# USB_DockingSTN.net
KiCad netlist of a schematic drawn in Altium Designer
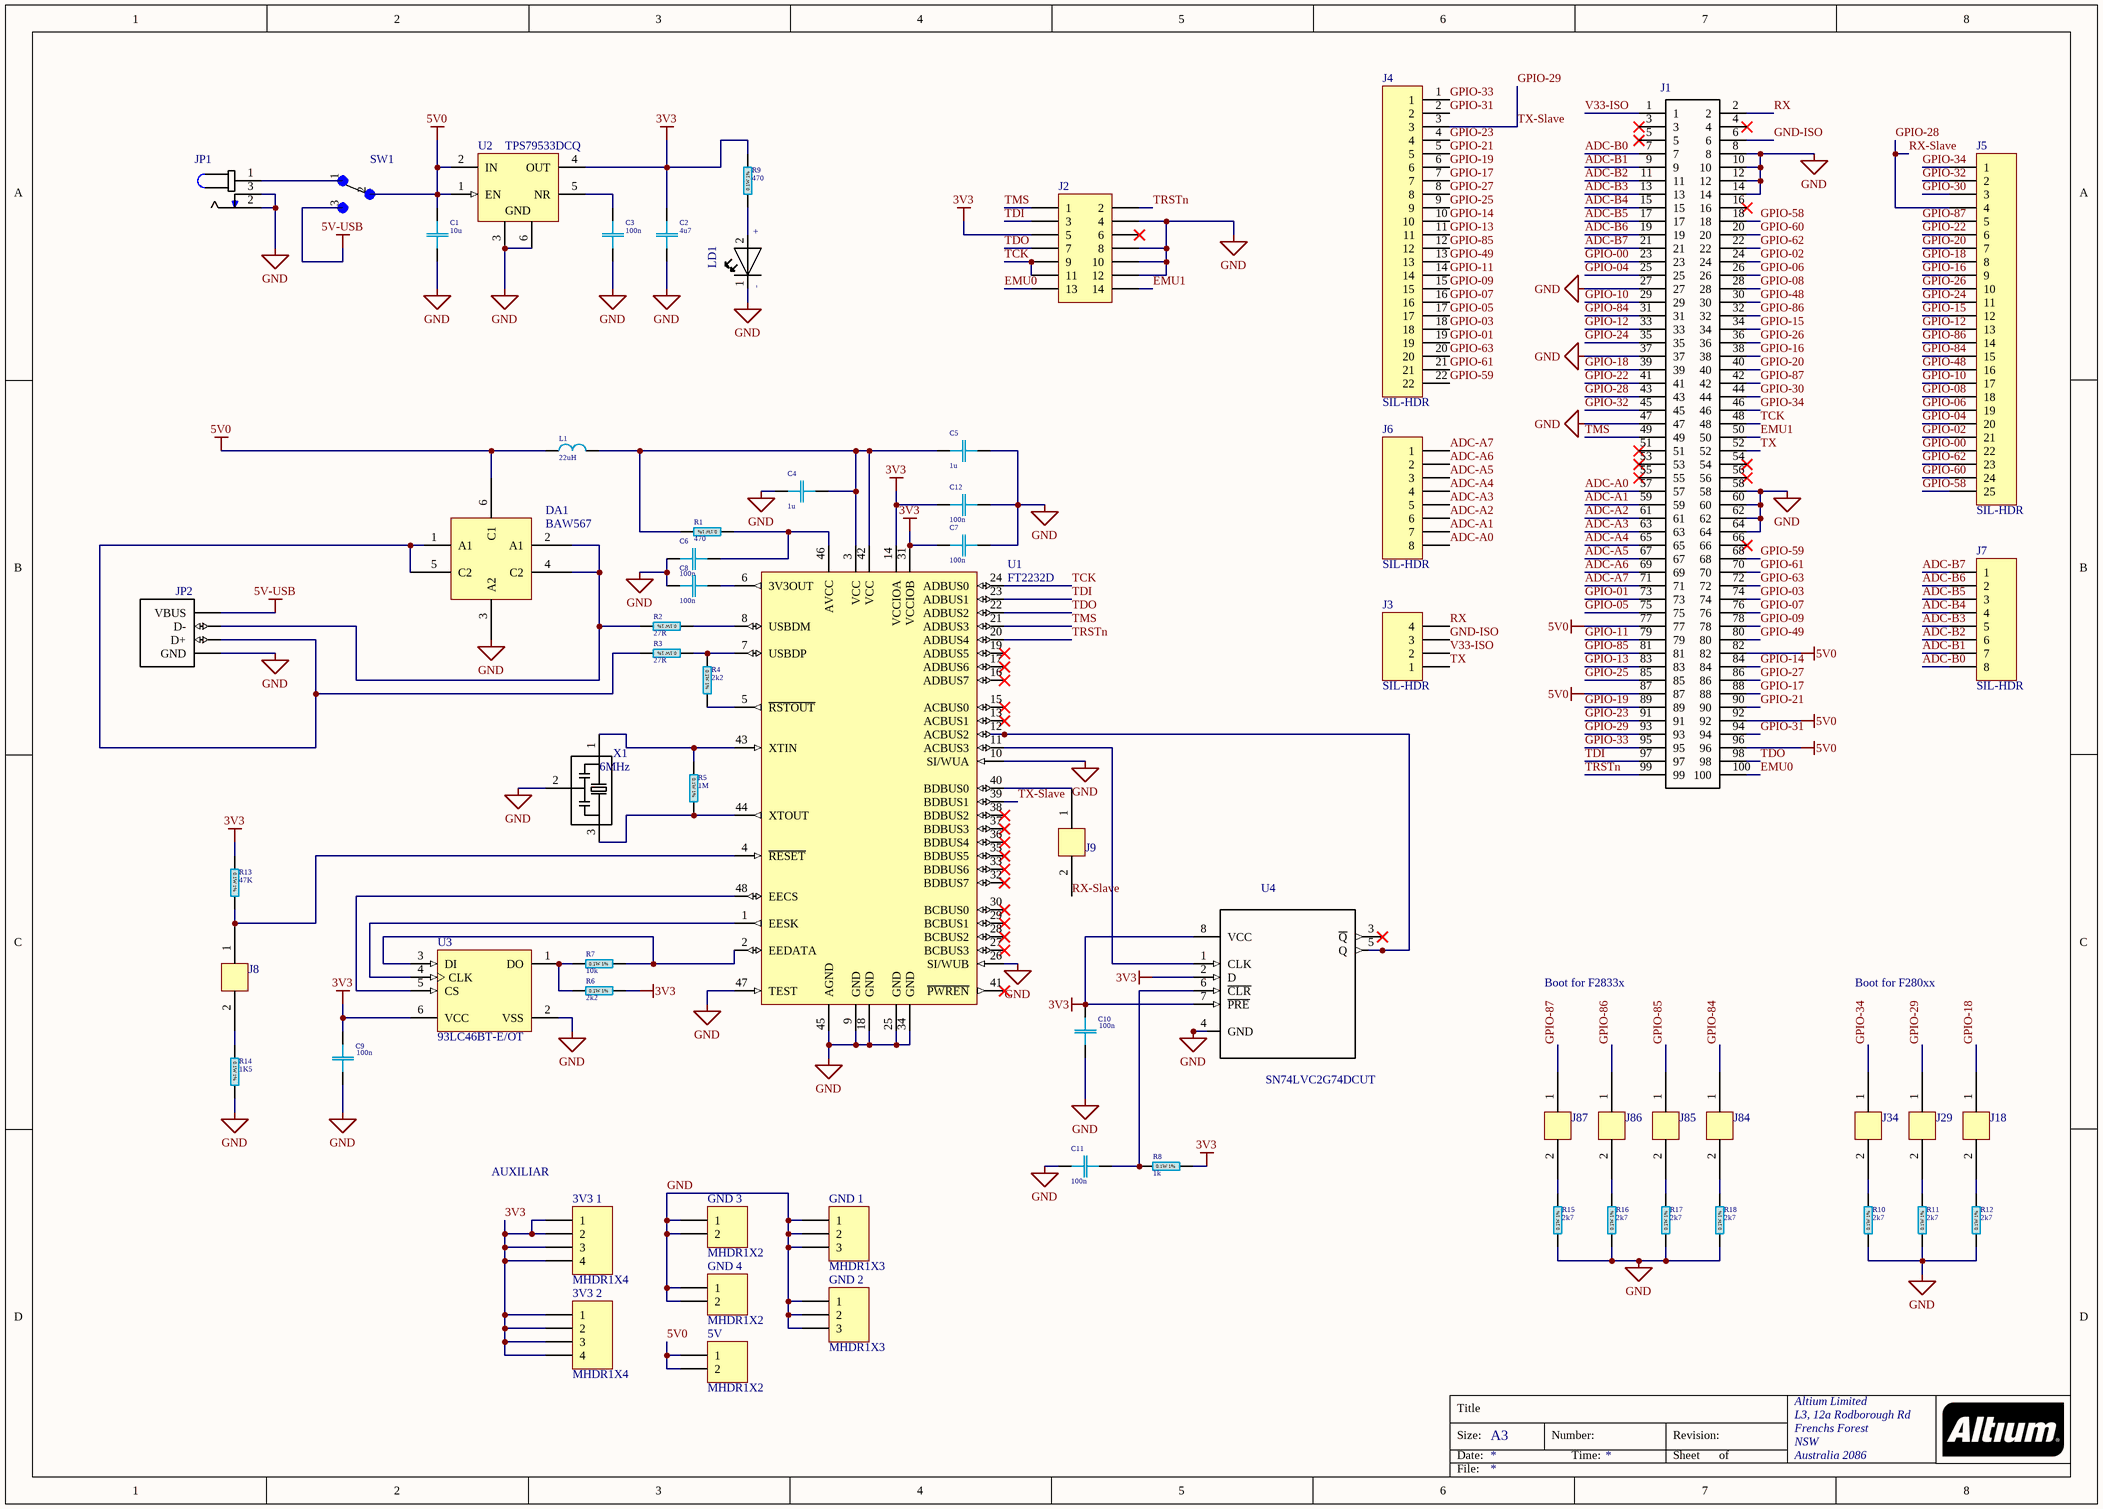
[diagram p0: USB_DockingSTN.SchDoc]

(export (version "E")
  (design (tool "Eeschema 10.0.6"))
  (components
    (comp (ref "3V3 1")
      (value "MHDR1X4")
      (footprint "MHDR1X4")
      (description "Header, 4-Pin")
      (fields (field (name "PUBLISHER") "Altium Limited"))
      (libsource (lib "Miscellaneous Connectors") (part "MHDR1X4"))
    )
    (comp (ref "3V3 2")
      (value "MHDR1X4")
      (footprint "MHDR1X4")
      (description "Header, 4-Pin")
      (fields (field (name "PUBLISHER") "Altium Limited"))
      (libsource (lib "Miscellaneous Connectors") (part "MHDR1X4"))
    )
    (comp (ref "5V")
      (value "MHDR1X2")
      (footprint "MHDR1X2")
      (description "Header, 2-Pin")
      (fields (field (name "PUBLISHER") "Altium Limited"))
      (libsource (lib "Miscellaneous Connectors") (part "MHDR1X2"))
    )
    (comp (ref "C1")
      (value "10u")
      (footprint "C 0805(2012)x0.65")
      (description "SMD-0805   100V X7R 10%")
      (fields
        (field (name "PART NUMBER") "CL21B103KCNC")
        (field (name "MANUFACTURER") "Samsung")
        (field (name "PUBLISHER") "Hefest")
      )
      (libsource (lib "SMD-Passive_ShareAppsCrack.com") (part "C 0805  100V X7R - 10n"))
    )
    (comp (ref "C2")
      (value "~")
      (footprint "C 0805(2012)x0.65")
      (description "SMD-0805   100V X7R 10%")
      (fields
        (field (name "PART NUMBER") "CL21B103KCNC")
        (field (name "MANUFACTURER") "Samsung")
        (field (name "0N") "4u7")
        (field (name "PUBLISHER") "Hefest")
      )
      (libsource (lib "SMD-Passive_ShareAppsCrack.com") (part "C 0805  100V X7R - 10n"))
    )
    (comp (ref "C3")
      (value "~")
      (footprint "C 0805(2012)x0.65")
      (description "SMD-0805   100V X7R 10%")
      (fields
        (field (name "PART NUMBER") "CL21B103KCNC")
        (field (name "MANUFACTURER") "Samsung")
        (field (name "0N") "100n")
        (field (name "PUBLISHER") "Hefest")
      )
      (libsource (lib "SMD-Passive_ShareAppsCrack.com") (part "C 0805  100V X7R - 10n"))
    )
    (comp (ref "C4")
      (value "1u")
      (footprint "C 0603(1608)x0.8")
      (description "SMD-0603     16V X5R 10%")
      (fields (field (name "MANUFACTURER") "Samsung") (field (name "PUBLISHER") "Hefest"))
      (libsource (lib "SMD-Passive_ShareAppsCrack.com") (part "C 0603    16V X7R - 1u"))
    )
    (comp (ref "C5")
      (value "1u")
      (footprint "C 0603(1608)x0.8")
      (description "SMD-0603     16V X5R 10%")
      (fields (field (name "MANUFACTURER") "Samsung") (field (name "PUBLISHER") "Hefest"))
      (libsource (lib "SMD-Passive_ShareAppsCrack.com") (part "C 0603    16V X7R - 1u"))
    )
    (comp (ref "C6")
      (value "100n")
      (footprint "C 0603(1608)x0.8")
      (description "SMD-0603     16V X5R 10%")
      (fields (field (name "MANUFACTURER") "Samsung") (field (name "PUBLISHER") "Hefest"))
      (libsource (lib "SMD-Passive_ShareAppsCrack.com") (part "C 0603    16V X7R - 1u"))
    )
    (comp (ref "C7")
      (value "100n")
      (footprint "C 0603(1608)x0.8")
      (description "SMD-0603     16V X5R 10%")
      (fields (field (name "MANUFACTURER") "Samsung") (field (name "PUBLISHER") "Hefest"))
      (libsource (lib "SMD-Passive_ShareAppsCrack.com") (part "C 0603    16V X7R - 1u"))
    )
    (comp (ref "C8")
      (value "100n")
      (footprint "C 0603(1608)x0.8")
      (description "SMD-0603     16V X5R 10%")
      (fields (field (name "MANUFACTURER") "Samsung") (field (name "PUBLISHER") "Hefest"))
      (libsource (lib "SMD-Passive_ShareAppsCrack.com") (part "C 0603    16V X7R - 1u"))
    )
    (comp (ref "C9")
      (value "100n")
      (footprint "C 0603(1608)x0.8")
      (description "SMD-0603     16V X5R 10%")
      (fields (field (name "MANUFACTURER") "Samsung") (field (name "PUBLISHER") "Hefest"))
      (libsource (lib "SMD-Passive_ShareAppsCrack.com") (part "C 0603    16V X7R - 1u"))
    )
    (comp (ref "C10")
      (value "100n")
      (footprint "C 0603(1608)x0.8")
      (description "SMD-0603     16V X5R 10%")
      (fields (field (name "MANUFACTURER") "Samsung") (field (name "PUBLISHER") "Hefest"))
      (libsource (lib "SMD-Passive_ShareAppsCrack.com") (part "C 0603    16V X7R - 1u"))
    )
    (comp (ref "C11")
      (value "100n")
      (footprint "C 0603(1608)x0.8")
      (description "SMD-0603     16V X5R 10%")
      (fields (field (name "MANUFACTURER") "Samsung") (field (name "PUBLISHER") "Hefest"))
      (libsource (lib "SMD-Passive_ShareAppsCrack.com") (part "C 0603    16V X7R - 1u"))
    )
    (comp (ref "C12")
      (value "100n")
      (footprint "C 0603(1608)x0.8")
      (description "SMD-0603     16V X5R 10%")
      (fields (field (name "MANUFACTURER") "Samsung") (field (name "PUBLISHER") "Hefest"))
      (libsource (lib "SMD-Passive_ShareAppsCrack.com") (part "C 0603    16V X7R - 1u"))
    )
    (comp (ref "DA1") (value "BAW567") (footprint "BAW567") (libsource (lib "Schlib2") (part "A1")))
    (comp (ref "GND 1")
      (value "MHDR1X3")
      (footprint "MHDR1X3")
      (description "Header, 3-Pin")
      (fields (field (name "PUBLISHER") "Altium Limited"))
      (libsource (lib "Miscellaneous Connectors") (part "MHDR1X3"))
    )
    (comp (ref "GND 2")
      (value "MHDR1X3")
      (footprint "MHDR1X3")
      (description "Header, 3-Pin")
      (fields (field (name "PUBLISHER") "Altium Limited"))
      (libsource (lib "Miscellaneous Connectors") (part "MHDR1X3"))
    )
    (comp (ref "GND 3")
      (value "MHDR1X2")
      (footprint "MHDR1X2")
      (description "Header, 2-Pin")
      (fields (field (name "PUBLISHER") "Altium Limited"))
      (libsource (lib "Miscellaneous Connectors") (part "MHDR1X2"))
    )
    (comp (ref "GND 4")
      (value "MHDR1X2")
      (footprint "MHDR1X2")
      (description "Header, 2-Pin")
      (fields (field (name "PUBLISHER") "Altium Limited"))
      (libsource (lib "Miscellaneous Connectors") (part "MHDR1X2"))
    )
    (comp (ref "J1")
      (value "5390213-1")
      (footprint "*TE_5390213-1")
      (description "D2P,100 POS,3.3V,NB DRAM,PB-FREE")
      (fields (field (name "MF") "TE Connectivity"))
      (libsource (lib "5390213-1") (part "5390213-1"))
    )
    (comp (ref "J2")
      (value "MHDR2X7")
      (footprint "MHDR2X7")
      (description "Header, 7-Pin, Dual row")
      (fields (field (name "PUBLISHER") "Altium Limited"))
      (libsource (lib "Miscellaneous Connectors") (part "MHDR2X7"))
    )
    (comp (ref "J3")
      (value "SIL-HDR")
      (footprint "MHDR1X4")
      (description "Header, 4-Pin")
      (fields (field (name "PUBLISHER") "Altium Limited"))
      (libsource (lib "") (part "MHDR1X4_1"))
    )
    (comp (ref "J4")
      (value "SIL-HDR")
      (footprint "PIN22")
      (description "22-Pin Edge Connector")
      (fields (field (name "PUBLISHER") "Altium Limited"))
      (libsource (lib "Miscellaneous Connectors") (part "Edge Con 22"))
    )
    (comp (ref "J5")
      (value "SIL-HDR")
      (footprint "HDR1X25")
      (description "Header, 25-Pin")
      (fields (field (name "PUBLISHER") "Altium Limited"))
      (libsource (lib "Miscellaneous Connectors") (part "Header 25"))
    )
    (comp (ref "J6")
      (value "SIL-HDR")
      (footprint "MHDR1X8")
      (description "Header, 8-Pin")
      (fields (field (name "PUBLISHER") "Altium Limited"))
      (libsource (lib "Miscellaneous Connectors") (part "MHDR1X8"))
    )
    (comp (ref "J7")
      (value "SIL-HDR")
      (footprint "MHDR1X8")
      (description "Header, 8-Pin")
      (fields (field (name "PUBLISHER") "Altium Limited"))
      (libsource (lib "") (part "MHDR1X8_1"))
    )
    (comp (ref "J8")
      (value "~")
      (footprint "PCBComponent_1")
      (libsource (lib "connector 2") (part "Component_1"))
    )
    (comp (ref "J9")
      (value "J9")
      (footprint "PCBComponent_1")
      (libsource (lib "connector 2") (part "Component_1"))
    )
    (comp (ref "J18")
      (value "~")
      (footprint "PCBComponent_1")
      (libsource (lib "connector 2") (part "Component_1"))
    )
    (comp (ref "J29")
      (value "~")
      (footprint "PCBComponent_1")
      (libsource (lib "connector 2") (part "Component_1"))
    )
    (comp (ref "J34")
      (value "~")
      (footprint "PCBComponent_1")
      (libsource (lib "connector 2") (part "Component_1"))
    )
    (comp (ref "J84")
      (value "~")
      (footprint "PCBComponent_1")
      (libsource (lib "connector 2") (part "Component_1"))
    )
    (comp (ref "J85")
      (value "~")
      (footprint "PCBComponent_1")
      (libsource (lib "connector 2") (part "Component_1"))
    )
    (comp (ref "J86")
      (value "~")
      (footprint "PCBComponent_1")
      (libsource (lib "connector 2") (part "Component_1"))
    )
    (comp (ref "J87")
      (value "~")
      (footprint "PCBComponent_1")
      (libsource (lib "connector 2") (part "Component_1"))
    )
    (comp (ref "JP1")
      (value "PJ-002BH")
      (footprint "*CUI_PJ-002BH")
      (description "2.5 x 6.5 mm, 5.0 A, Horizontal, Through Hole, Dc Power Jack Connector")
      (fields (field (name "MF") "CUI Devices") (field (name "DIGI-KEY_PART_NUMBER") "CP-002BH-ND"))
      (libsource (lib "PJ-002BH") (part "PJ-002BH"))
    )
    (comp (ref "JP2")
      (value "292304-1")
      (footprint "*TE_292304-1")
      (description "USB - B USB 2.0 Receptacle Connector 4 Position Through Hole, Right Angle")
      (fields (field (name "MF") "TE Connectivity"))
      (libsource (lib "292304-1") (part "292304-1"))
    )
    (comp (ref "L1")
      (value "22uH")
      (footprint "L 0805(2012)")
      (description "SMD 0805 Q-65 @150MHz")
      (fields
        (field (name "PART NUMBER") "CCFH0805 C R10J")
        (field (name "MANUFACTURER") "COILS")
        (field (name "PUBLISHER") "Hefest")
      )
      (libsource (lib "SMD-Passive_ShareAppsCrack.com") (part "L 0805 100n"))
    )
    (comp (ref "LD1")
      (value "WL-SMCW")
      (footprint "*WL-SMCW_0603")
      (description "LED, 0805, B GREEN, 40MCD, 570NM; Bulb Size: -; LED Colour: Green; Luminous Intens")
      (fields (field (name "MF") "Wurth Electronics") (field (name "DIGI-KEY_PART_NUMBER") "732-4986-1-ND"))
      (libsource (lib "WL-SMCW") (part "WL-SMCW"))
    )
    (comp (ref "R1")
      (value "470")
      (footprint "R 0603(1608)")
      (description "SMD 0603 0.1W     5%   75V")
      (fields
        (field (name "MANUFACTURER") "YAGEO")
        (field (name "POWER") "0.1W")
        (field (name "PUBLISHER") "Hefest")
      )
      (libsource (lib "") (part "R 0603-5%_1"))
    )
    (comp (ref "R2")
      (value "27R")
      (footprint "R 0603(1608)")
      (description "SMD 0603 0.1W     5%   75V")
      (fields
        (field (name "MANUFACTURER") "YAGEO")
        (field (name "POWER") "0.1W")
        (field (name "PUBLISHER") "Hefest")
      )
      (libsource (lib "") (part "R 0603-5%_1"))
    )
    (comp (ref "R3")
      (value "27R")
      (footprint "R 0603(1608)")
      (description "SMD 0603 0.1W     5%   75V")
      (fields
        (field (name "MANUFACTURER") "YAGEO")
        (field (name "POWER") "0.1W")
        (field (name "PUBLISHER") "Hefest")
      )
      (libsource (lib "") (part "R 0603-5%_1"))
    )
    (comp (ref "R4")
      (value "2k2")
      (footprint "R 0603(1608)")
      (description "SMD 0603 0.1W     5%   75V")
      (fields
        (field (name "MANUFACTURER") "YAGEO")
        (field (name "POWER") "0.1W")
        (field (name "PUBLISHER") "Hefest")
      )
      (libsource (lib "SMD-Passive_ShareAppsCrack.com") (part "R 0603-5%"))
    )
    (comp (ref "R5")
      (value "1M")
      (footprint "R 0603(1608)")
      (description "SMD 0603 0.1W     5%   75V")
      (fields
        (field (name "MANUFACTURER") "YAGEO")
        (field (name "POWER") "0.1W")
        (field (name "PUBLISHER") "Hefest")
      )
      (libsource (lib "SMD-Passive_ShareAppsCrack.com") (part "R 0603-5%"))
    )
    (comp (ref "R6")
      (value "2k2")
      (footprint "R 0603(1608)")
      (description "SMD 0603 0.1W     5%   75V")
      (fields
        (field (name "MANUFACTURER") "YAGEO")
        (field (name "POWER") "0.1W")
        (field (name "PUBLISHER") "Hefest")
      )
      (libsource (lib "") (part "R 0603-5%_2"))
    )
    (comp (ref "R7")
      (value "10k")
      (footprint "R 0603(1608)")
      (description "SMD 0603 0.1W     5%   75V")
      (fields
        (field (name "MANUFACTURER") "YAGEO")
        (field (name "POWER") "0.1W")
        (field (name "PUBLISHER") "Hefest")
      )
      (libsource (lib "") (part "R 0603-5%_2"))
    )
    (comp (ref "R8")
      (value "1k")
      (footprint "R 0603(1608)")
      (description "SMD 0603 0.1W     5%   75V")
      (fields
        (field (name "MANUFACTURER") "YAGEO")
        (field (name "POWER") "0.1W")
        (field (name "PUBLISHER") "Hefest")
      )
      (libsource (lib "") (part "R 0603-5%_2"))
    )
    (comp (ref "R9")
      (value "470")
      (footprint "R 0603(1608)")
      (description "SMD 0603 0.1W     5%   75V")
      (fields
        (field (name "MANUFACTURER") "YAGEO")
        (field (name "POWER") "0.1W")
        (field (name "PUBLISHER") "Hefest")
      )
      (libsource (lib "") (part "R 0603-5%_3"))
    )
    (comp (ref "R10")
      (value "2k7")
      (footprint "R 0603(1608)")
      (description "SMD 0603 0.1W     5%   75V")
      (fields
        (field (name "MANUFACTURER") "YAGEO")
        (field (name "POWER") "0.1W")
        (field (name "PUBLISHER") "Hefest")
      )
      (libsource (lib "") (part "R 0603-5%_3"))
    )
    (comp (ref "R11")
      (value "2k7")
      (footprint "R 0603(1608)")
      (description "SMD 0603 0.1W     5%   75V")
      (fields
        (field (name "MANUFACTURER") "YAGEO")
        (field (name "POWER") "0.1W")
        (field (name "PUBLISHER") "Hefest")
      )
      (libsource (lib "") (part "R 0603-5%_3"))
    )
    (comp (ref "R12")
      (value "2k7")
      (footprint "R 0603(1608)")
      (description "SMD 0603 0.1W     5%   75V")
      (fields
        (field (name "MANUFACTURER") "YAGEO")
        (field (name "POWER") "0.1W")
        (field (name "PUBLISHER") "Hefest")
      )
      (libsource (lib "") (part "R 0603-5%_3"))
    )
    (comp (ref "R13")
      (value "47K")
      (footprint "R 0603(1608)")
      (description "SMD 0603 0.1W     5%   75V")
      (fields
        (field (name "MANUFACTURER") "YAGEO")
        (field (name "POWER") "0.1W")
        (field (name "PUBLISHER") "Hefest")
      )
      (libsource (lib "SMD-Passive_ShareAppsCrack.com") (part "R 0603-5%"))
    )
    (comp (ref "R14")
      (value "1K5")
      (footprint "R 0603(1608)")
      (description "SMD 0603 0.1W     5%   75V")
      (fields
        (field (name "MANUFACTURER") "YAGEO")
        (field (name "POWER") "0.1W")
        (field (name "PUBLISHER") "Hefest")
      )
      (libsource (lib "SMD-Passive_ShareAppsCrack.com") (part "R 0603-5%"))
    )
    (comp (ref "R15")
      (value "2k7")
      (footprint "R 0603(1608)")
      (description "SMD 0603 0.1W     5%   75V")
      (fields
        (field (name "MANUFACTURER") "YAGEO")
        (field (name "POWER") "0.1W")
        (field (name "PUBLISHER") "Hefest")
      )
      (libsource (lib "") (part "R 0603-5%_3"))
    )
    (comp (ref "R16")
      (value "2k7")
      (footprint "R 0603(1608)")
      (description "SMD 0603 0.1W     5%   75V")
      (fields
        (field (name "MANUFACTURER") "YAGEO")
        (field (name "POWER") "0.1W")
        (field (name "PUBLISHER") "Hefest")
      )
      (libsource (lib "") (part "R 0603-5%_3"))
    )
    (comp (ref "R17")
      (value "2k7")
      (footprint "R 0603(1608)")
      (description "SMD 0603 0.1W     5%   75V")
      (fields
        (field (name "MANUFACTURER") "YAGEO")
        (field (name "POWER") "0.1W")
        (field (name "PUBLISHER") "Hefest")
      )
      (libsource (lib "") (part "R 0603-5%_3"))
    )
    (comp (ref "R18")
      (value "2k7")
      (footprint "R 0603(1608)")
      (description "SMD 0603 0.1W     5%   75V")
      (fields
        (field (name "MANUFACTURER") "YAGEO")
        (field (name "POWER") "0.1W")
        (field (name "PUBLISHER") "Hefest")
      )
      (libsource (lib "") (part "R 0603-5%_3"))
    )
    (comp (ref "SW1")
      (value "400BWMSP1R2BLKSM6QE")
      (footprint "*SW_400BWMSP1R2BLKSM6QE")
      (description "400B Series 3 A SPDT On-None-On Surface Mount Sub-Miniature Rocker Switch")
      (fields (field (name "MF") "E-Switch"))
      (libsource (lib "400BWMSP1R2BLKSM6QE") (part "400BWMSP1R2BLKSM6QE"))
    )
    (comp (ref "U1")
      (value "FT2232D")
      (footprint "LQFP-48_N")
      (description "FT2232D Dual USB to Serial UART/FIFO IC, -40 to +85 degC, 48-pin LQFP")
      (fields (field (name "MANUFACTURER") "FTDI"))
      (libsource (lib "FTDI FT Series") (part "FT2232D"))
    )
    (comp (ref "U2")
      (value "TPS79533DCQ")
      (footprint "TI-DCQ6_N")
      (fields (field (name "MANUFACTURER") "Texas Instruments"))
      (libsource (lib "TI Power Management Linear Regulator Single Channel LDO (400-7500mA)") (part "TPS79533DCQ"))
    )
    (comp (ref "U3")
      (value "93LC46BT-E/OT")
      (footprint "SOT-23-OT6_N")
      (description "1K, 64x16-bit, 2.5V Microwire Serial EEPROM, 6-Pin SOT-23, Extended Temperature, Tape and Reel")
      (fields (field (name "MANUFACTURER") "Microchip"))
      (libsource (lib "Microchip Microwire Serial EEPROM") (part "93LC46BT-E/OT"))
    )
    (comp (ref "U4")
      (value "SN74LVC2G74DCUT")
      (footprint "*SOP50P310X90-8N")
      (description "Single Positive-Edge-Triggered D-Type Flip-Flop with Clear and Preset 8-VSSOP -40 to 125")
      (fields (field (name "DIGI-KEY_PART_NUMBER") "296-26623-1-ND") (field (name "MF") "Texas Instruments"))
      (libsource (lib "SN74LVC2G74DCUT") (part "SN74LVC2G74DCUT"))
    )
    (comp (ref "X1")
      (value "~")
      (footprint "*OSC_CSTCR4M00G53-R0")
      (description "Ceramic Resonator 4MHz ??0.5% _Tol_ ??0.2% _Stability_ 15pF 60Ohm 3-Pin CSMD T/R")
      (fields (field (name "MP") "CSTCR4M00G53-R0") (field (name "MF") "Murata"))
      (libsource (lib "CSTCR4M00G53-R0") (part "CSTCR4M00G53-R0"))
    )
  )
  (nets
    (net (code "1") (name "/ADC-A0") (class "Default")
      (node (ref "J1") (pin "57") (pinfunction "57_57") (pintype "passive"))
      (node (ref "J6") (pin "8") (pinfunction "8_8") (pintype "passive"))
    )
    (net (code "2") (name "/ADC-A1") (class "Default")
      (node (ref "J1") (pin "59") (pinfunction "59_59") (pintype "passive"))
      (node (ref "J6") (pin "7") (pinfunction "7_7") (pintype "passive"))
    )
    (net (code "3") (name "/ADC-A2") (class "Default")
      (node (ref "J1") (pin "61") (pinfunction "61_61") (pintype "passive"))
      (node (ref "J6") (pin "6") (pinfunction "6_6") (pintype "passive"))
    )
    (net (code "4") (name "/ADC-A3") (class "Default")
      (node (ref "J1") (pin "63") (pinfunction "63_63") (pintype "passive"))
      (node (ref "J6") (pin "5") (pinfunction "5_5") (pintype "passive"))
    )
    (net (code "5") (name "/ADC-A4") (class "Default")
      (node (ref "J1") (pin "65") (pinfunction "65_65") (pintype "passive"))
      (node (ref "J6") (pin "4") (pinfunction "4_4") (pintype "passive"))
    )
    (net (code "6") (name "/ADC-A5") (class "Default")
      (node (ref "J1") (pin "67") (pinfunction "67_67") (pintype "passive"))
      (node (ref "J6") (pin "3") (pinfunction "3_3") (pintype "passive"))
    )
    (net (code "7") (name "/ADC-A6") (class "Default")
      (node (ref "J1") (pin "69") (pinfunction "69_69") (pintype "passive"))
      (node (ref "J6") (pin "2") (pinfunction "2_2") (pintype "passive"))
    )
    (net (code "8") (name "/ADC-A7") (class "Default")
      (node (ref "J1") (pin "71") (pinfunction "71_71") (pintype "passive"))
      (node (ref "J6") (pin "1") (pinfunction "1_1") (pintype "passive"))
    )
    (net (code "9") (name "/ADC-B0") (class "Default")
      (node (ref "J1") (pin "7") (pinfunction "7_7") (pintype "passive"))
      (node (ref "J7") (pin "8") (pinfunction "8_8") (pintype "passive"))
    )
    (net (code "10") (name "/ADC-B1") (class "Default")
      (node (ref "J1") (pin "9") (pinfunction "9_9") (pintype "passive"))
      (node (ref "J7") (pin "7") (pinfunction "7_7") (pintype "passive"))
    )
    (net (code "11") (name "/ADC-B2") (class "Default")
      (node (ref "J1") (pin "11") (pinfunction "11_11") (pintype "passive"))
      (node (ref "J7") (pin "6") (pinfunction "6_6") (pintype "passive"))
    )
    (net (code "12") (name "/ADC-B3") (class "Default")
      (node (ref "J1") (pin "13") (pinfunction "13_13") (pintype "passive"))
      (node (ref "J7") (pin "5") (pinfunction "5_5") (pintype "passive"))
    )
    (net (code "13") (name "/ADC-B4") (class "Default")
      (node (ref "J1") (pin "15") (pinfunction "15_15") (pintype "passive"))
      (node (ref "J7") (pin "4") (pinfunction "4_4") (pintype "passive"))
    )
    (net (code "14") (name "/ADC-B5") (class "Default")
      (node (ref "J1") (pin "17") (pinfunction "17_17") (pintype "passive"))
      (node (ref "J7") (pin "3") (pinfunction "3_3") (pintype "passive"))
    )
    (net (code "15") (name "/ADC-B6") (class "Default")
      (node (ref "J1") (pin "19") (pinfunction "19_19") (pintype "passive"))
      (node (ref "J7") (pin "2") (pinfunction "2_2") (pintype "passive"))
    )
    (net (code "16") (name "/ADC-B7") (class "Default")
      (node (ref "J1") (pin "21") (pinfunction "21_21") (pintype "passive"))
      (node (ref "J7") (pin "1") (pinfunction "1_1") (pintype "passive"))
    )
    (net (code "17") (name "/EMU0") (class "Default")
      (node (ref "J1") (pin "100") (pinfunction "100_100") (pintype "passive"))
      (node (ref "J2") (pin "13") (pinfunction "13_13") (pintype "passive"))
    )
    (net (code "18") (name "/EMU1") (class "Default")
      (node (ref "J1") (pin "50") (pinfunction "50_50") (pintype "passive"))
      (node (ref "J2") (pin "14") (pinfunction "14_14") (pintype "passive"))
    )
    (net (code "19") (name "/GND-ISO") (class "Default")
      (node (ref "J1") (pin "6") (pinfunction "6_6") (pintype "passive"))
      (node (ref "J3") (pin "3") (pinfunction "3_3") (pintype "passive"))
    )
    (net (code "20") (name "/GPIO-00") (class "Default")
      (node (ref "J1") (pin "23") (pinfunction "23_23") (pintype "passive"))
      (node (ref "J5") (pin "22") (pinfunction "22_22") (pintype "passive"))
    )
    (net (code "21") (name "/GPIO-01") (class "Default")
      (node (ref "J1") (pin "73") (pinfunction "73_73") (pintype "passive"))
      (node (ref "J4") (pin "19") (pinfunction "19_19") (pintype "passive"))
    )
    (net (code "22") (name "/GPIO-02") (class "Default")
      (node (ref "J1") (pin "24") (pinfunction "24_24") (pintype "passive"))
      (node (ref "J5") (pin "21") (pinfunction "21_21") (pintype "passive"))
    )
    (net (code "23") (name "/GPIO-03") (class "Default")
      (node (ref "J1") (pin "74") (pinfunction "74_74") (pintype "passive"))
      (node (ref "J4") (pin "18") (pinfunction "18_18") (pintype "passive"))
    )
    (net (code "24") (name "/GPIO-04") (class "Default")
      (node (ref "J1") (pin "25") (pinfunction "25_25") (pintype "passive"))
      (node (ref "J5") (pin "20") (pinfunction "20_20") (pintype "passive"))
    )
    (net (code "25") (name "/GPIO-05") (class "Default")
      (node (ref "J1") (pin "75") (pinfunction "75_75") (pintype "passive"))
      (node (ref "J4") (pin "17") (pinfunction "17_17") (pintype "passive"))
    )
    (net (code "26") (name "/GPIO-06") (class "Default")
      (node (ref "J1") (pin "26") (pinfunction "26_26") (pintype "passive"))
      (node (ref "J5") (pin "19") (pinfunction "19_19") (pintype "passive"))
    )
    (net (code "27") (name "/GPIO-07") (class "Default")
      (node (ref "J1") (pin "76") (pinfunction "76_76") (pintype "passive"))
      (node (ref "J4") (pin "16") (pinfunction "16_16") (pintype "passive"))
    )
    (net (code "28") (name "/GPIO-08") (class "Default")
      (node (ref "J1") (pin "28") (pinfunction "28_28") (pintype "passive"))
      (node (ref "J5") (pin "18") (pinfunction "18_18") (pintype "passive"))
    )
    (net (code "29") (name "/GPIO-09") (class "Default")
      (node (ref "J1") (pin "78") (pinfunction "78_78") (pintype "passive"))
      (node (ref "J4") (pin "15") (pinfunction "15_15") (pintype "passive"))
    )
    (net (code "30") (name "/GPIO-10") (class "Default")
      (node (ref "J1") (pin "29") (pinfunction "29_29") (pintype "passive"))
      (node (ref "J5") (pin "17") (pinfunction "17_17") (pintype "passive"))
    )
    (net (code "31") (name "/GPIO-11") (class "Default")
      (node (ref "J1") (pin "79") (pinfunction "79_79") (pintype "passive"))
      (node (ref "J4") (pin "14") (pinfunction "14_14") (pintype "passive"))
    )
    (net (code "32") (name "/GPIO-12") (class "Default")
      (node (ref "J1") (pin "33") (pinfunction "33_33") (pintype "passive"))
      (node (ref "J5") (pin "13") (pinfunction "13_13") (pintype "passive"))
    )
    (net (code "33") (name "/GPIO-13") (class "Default")
      (node (ref "J1") (pin "83") (pinfunction "83_83") (pintype "passive"))
      (node (ref "J4") (pin "11") (pinfunction "11_11") (pintype "passive"))
    )
    (net (code "34") (name "/GPIO-14") (class "Default")
      (node (ref "J1") (pin "84") (pinfunction "84_84") (pintype "passive"))
      (node (ref "J4") (pin "10") (pinfunction "10_10") (pintype "passive"))
    )
    (net (code "35") (name "/GPIO-15") (class "Default")
      (node (ref "J1") (pin "34") (pinfunction "34_34") (pintype "passive"))
      (node (ref "J5") (pin "12") (pinfunction "12_12") (pintype "passive"))
    )
    (net (code "36") (name "/GPIO-16") (class "Default")
      (node (ref "J1") (pin "38") (pinfunction "38_38") (pintype "passive"))
      (node (ref "J5") (pin "9") (pinfunction "9_9") (pintype "passive"))
    )
    (net (code "37") (name "/GPIO-17") (class "Default")
      (node (ref "J1") (pin "88") (pinfunction "88_88") (pintype "passive"))
      (node (ref "J4") (pin "7") (pinfunction "7_7") (pintype "passive"))
    )
    (net (code "38") (name "/GPIO-18") (class "Default")
      (node (ref "J1") (pin "39") (pinfunction "39_39") (pintype "passive"))
      (node (ref "J18") (pin "1") (pinfunction "1_1") (pintype "passive"))
      (node (ref "J5") (pin "8") (pinfunction "8_8") (pintype "passive"))
    )
    (net (code "39") (name "/GPIO-19") (class "Default")
      (node (ref "J1") (pin "89") (pinfunction "89_89") (pintype "passive"))
      (node (ref "J4") (pin "6") (pinfunction "6_6") (pintype "passive"))
    )
    (net (code "40") (name "/GPIO-20") (class "Default")
      (node (ref "J1") (pin "40") (pinfunction "40_40") (pintype "passive"))
      (node (ref "J5") (pin "7") (pinfunction "7_7") (pintype "passive"))
    )
    (net (code "41") (name "/GPIO-21") (class "Default")
      (node (ref "J1") (pin "90") (pinfunction "90_90") (pintype "passive"))
      (node (ref "J4") (pin "5") (pinfunction "5_5") (pintype "passive"))
    )
    (net (code "42") (name "/GPIO-22") (class "Default")
      (node (ref "J1") (pin "41") (pinfunction "41_41") (pintype "passive"))
      (node (ref "J5") (pin "6") (pinfunction "6_6") (pintype "passive"))
    )
    (net (code "43") (name "/GPIO-23") (class "Default")
      (node (ref "J1") (pin "91") (pinfunction "91_91") (pintype "passive"))
      (node (ref "J4") (pin "4") (pinfunction "4_4") (pintype "passive"))
    )
    (net (code "44") (name "/GPIO-24") (class "Default")
      (node (ref "J1") (pin "35") (pinfunction "35_35") (pintype "passive"))
      (node (ref "J5") (pin "11") (pinfunction "11_11") (pintype "passive"))
    )
    (net (code "45") (name "/GPIO-25") (class "Default")
      (node (ref "J1") (pin "85") (pinfunction "85_85") (pintype "passive"))
      (node (ref "J4") (pin "9") (pinfunction "9_9") (pintype "passive"))
    )
    (net (code "46") (name "/GPIO-26") (class "Default")
      (node (ref "J1") (pin "36") (pinfunction "36_36") (pintype "passive"))
      (node (ref "J5") (pin "10") (pinfunction "10_10") (pintype "passive"))
    )
    (net (code "47") (name "/GPIO-27") (class "Default")
      (node (ref "J1") (pin "86") (pinfunction "86_86") (pintype "passive"))
      (node (ref "J4") (pin "8") (pinfunction "8_8") (pintype "passive"))
    )
    (net (code "48") (name "/GPIO-28") (class "Default")
      (node (ref "J1") (pin "43") (pinfunction "43_43") (pintype "passive"))
      (node (ref "J5") (pin "4") (pinfunction "4_4") (pintype "passive"))
      (node (ref "J9") (pin "2") (pinfunction "2_2") (pintype "passive"))
    )
    (net (code "49") (name "/GPIO-29") (class "Default")
      (node (ref "J1") (pin "93") (pinfunction "93_93") (pintype "passive"))
      (node (ref "J29") (pin "1") (pinfunction "1_1") (pintype "passive"))
      (node (ref "J4") (pin "3") (pinfunction "3_3") (pintype "passive"))
      (node (ref "U1") (pin "39") (pinfunction "BDBUS1_39") (pintype "bidirectional"))
    )
    (net (code "50") (name "/GPIO-30") (class "Default")
      (node (ref "J1") (pin "44") (pinfunction "44_44") (pintype "passive"))
      (node (ref "J5") (pin "3") (pinfunction "3_3") (pintype "passive"))
    )
    (net (code "51") (name "/GPIO-31") (class "Default")
      (node (ref "J1") (pin "94") (pinfunction "94_94") (pintype "passive"))
      (node (ref "J4") (pin "2") (pinfunction "2_2") (pintype "passive"))
    )
    (net (code "52") (name "/GPIO-32") (class "Default")
      (node (ref "J1") (pin "45") (pinfunction "45_45") (pintype "passive"))
      (node (ref "J5") (pin "2") (pinfunction "2_2") (pintype "passive"))
    )
    (net (code "53") (name "/GPIO-33") (class "Default")
      (node (ref "J1") (pin "95") (pinfunction "95_95") (pintype "passive"))
      (node (ref "J4") (pin "1") (pinfunction "1_1") (pintype "passive"))
    )
    (net (code "54") (name "/GPIO-34") (class "Default")
      (node (ref "J1") (pin "46") (pinfunction "46_46") (pintype "passive"))
      (node (ref "J34") (pin "1") (pinfunction "1_1") (pintype "passive"))
      (node (ref "J5") (pin "1") (pinfunction "1_1") (pintype "passive"))
    )
    (net (code "55") (name "/GPIO-48") (class "Default")
      (node (ref "J1") (pin "30") (pinfunction "30_30") (pintype "passive"))
      (node (ref "J5") (pin "16") (pinfunction "16_16") (pintype "passive"))
    )
    (net (code "56") (name "/GPIO-49") (class "Default")
      (node (ref "J1") (pin "80") (pinfunction "80_80") (pintype "passive"))
      (node (ref "J4") (pin "13") (pinfunction "13_13") (pintype "passive"))
    )
    (net (code "57") (name "/GPIO-58") (class "Default")
      (node (ref "J1") (pin "18") (pinfunction "18_18") (pintype "passive"))
      (node (ref "J5") (pin "25") (pinfunction "25_25") (pintype "passive"))
    )
    (net (code "58") (name "/GPIO-59") (class "Default")
      (node (ref "J1") (pin "68") (pinfunction "68_68") (pintype "passive"))
      (node (ref "J4") (pin "22") (pinfunction "22_22") (pintype "passive"))
    )
    (net (code "59") (name "/GPIO-60") (class "Default")
      (node (ref "J1") (pin "20") (pinfunction "20_20") (pintype "passive"))
      (node (ref "J5") (pin "24") (pinfunction "24_24") (pintype "passive"))
    )
    (net (code "60") (name "/GPIO-61") (class "Default")
      (node (ref "J1") (pin "70") (pinfunction "70_70") (pintype "passive"))
      (node (ref "J4") (pin "21") (pinfunction "21_21") (pintype "passive"))
    )
    (net (code "61") (name "/GPIO-62") (class "Default")
      (node (ref "J1") (pin "22") (pinfunction "22_22") (pintype "passive"))
      (node (ref "J5") (pin "23") (pinfunction "23_23") (pintype "passive"))
    )
    (net (code "62") (name "/GPIO-63") (class "Default")
      (node (ref "J1") (pin "72") (pinfunction "72_72") (pintype "passive"))
      (node (ref "J4") (pin "20") (pinfunction "20_20") (pintype "passive"))
    )
    (net (code "63") (name "/GPIO-84") (class "Default")
      (node (ref "J1") (pin "31") (pinfunction "31_31") (pintype "passive"))
      (node (ref "J5") (pin "15") (pinfunction "15_15") (pintype "passive"))
      (node (ref "J84") (pin "1") (pinfunction "1_1") (pintype "passive"))
    )
    (net (code "64") (name "/GPIO-85") (class "Default")
      (node (ref "J1") (pin "81") (pinfunction "81_81") (pintype "passive"))
      (node (ref "J4") (pin "12") (pinfunction "12_12") (pintype "passive"))
      (node (ref "J85") (pin "1") (pinfunction "1_1") (pintype "passive"))
    )
    (net (code "65") (name "/GPIO-86") (class "Default")
      (node (ref "J1") (pin "32") (pinfunction "32_32") (pintype "passive"))
      (node (ref "J5") (pin "14") (pinfunction "14_14") (pintype "passive"))
      (node (ref "J86") (pin "1") (pinfunction "1_1") (pintype "passive"))
    )
    (net (code "66") (name "/GPIO-87") (class "Default")
      (node (ref "J1") (pin "42") (pinfunction "42_42") (pintype "passive"))
      (node (ref "J5") (pin "5") (pinfunction "5_5") (pintype "passive"))
      (node (ref "J87") (pin "1") (pinfunction "1_1") (pintype "passive"))
    )
    (net (code "67") (name "/RX") (class "Default")
      (node (ref "J1") (pin "2") (pinfunction "2_2") (pintype "passive"))
      (node (ref "J3") (pin "4") (pinfunction "4_4") (pintype "passive"))
    )
    (net (code "68") (name "/TCK") (class "Default")
      (node (ref "J1") (pin "48") (pinfunction "48_48") (pintype "passive"))
      (node (ref "J2") (pin "11") (pinfunction "11_11") (pintype "passive"))
      (node (ref "J2") (pin "9") (pinfunction "9_9") (pintype "passive"))
      (node (ref "U1") (pin "24") (pinfunction "ADBUS0_24") (pintype "bidirectional"))
    )
    (net (code "69") (name "/TDI") (class "Default")
      (node (ref "J1") (pin "97") (pinfunction "97_97") (pintype "passive"))
      (node (ref "J2") (pin "3") (pinfunction "3_3") (pintype "passive"))
      (node (ref "U1") (pin "23") (pinfunction "ADBUS1_23") (pintype "bidirectional"))
    )
    (net (code "70") (name "/TDO") (class "Default")
      (node (ref "J1") (pin "98") (pinfunction "98_98") (pintype "passive"))
      (node (ref "J2") (pin "7") (pinfunction "7_7") (pintype "passive"))
      (node (ref "U1") (pin "22") (pinfunction "ADBUS2_22") (pintype "bidirectional"))
    )
    (net (code "71") (name "/TMS") (class "Default")
      (node (ref "J1") (pin "49") (pinfunction "49_49") (pintype "passive"))
      (node (ref "J2") (pin "1") (pinfunction "1_1") (pintype "passive"))
      (node (ref "U1") (pin "21") (pinfunction "ADBUS3_21") (pintype "bidirectional"))
    )
    (net (code "72") (name "/TRSTn") (class "Default")
      (node (ref "J1") (pin "99") (pinfunction "99_99") (pintype "passive"))
      (node (ref "J2") (pin "2") (pinfunction "2_2") (pintype "passive"))
      (node (ref "U1") (pin "20") (pinfunction "ADBUS4_20") (pintype "bidirectional"))
    )
    (net (code "73") (name "/TX") (class "Default")
      (node (ref "J1") (pin "52") (pinfunction "52_52") (pintype "passive"))
      (node (ref "J3") (pin "1") (pinfunction "1_1") (pintype "passive"))
    )
    (net (code "74") (name "/V33-ISO") (class "Default")
      (node (ref "J1") (pin "1") (pinfunction "1_1") (pintype "passive"))
      (node (ref "J3") (pin "2") (pinfunction "2_2") (pintype "passive"))
    )
    (net (code "75") (name "3V3") (class "Default")
      (node (ref "3V3 1") (pin "1") (pinfunction "1_1") (pintype "passive"))
      (node (ref "3V3 1") (pin "2") (pinfunction "2_2") (pintype "passive"))
      (node (ref "3V3 1") (pin "3") (pinfunction "3_3") (pintype "passive"))
      (node (ref "3V3 1") (pin "4") (pinfunction "4_4") (pintype "passive"))
      (node (ref "3V3 2") (pin "1") (pinfunction "1_1") (pintype "passive"))
      (node (ref "3V3 2") (pin "2") (pinfunction "2_2") (pintype "passive"))
      (node (ref "3V3 2") (pin "3") (pinfunction "3_3") (pintype "passive"))
      (node (ref "3V3 2") (pin "4") (pinfunction "4_4") (pintype "passive"))
      (node (ref "C10") (pin "2") (pinfunction "2_2") (pintype "passive"))
      (node (ref "C12") (pin "1") (pinfunction "1_1") (pintype "passive"))
      (node (ref "C2") (pin "1") (pinfunction "1_1") (pintype "passive"))
      (node (ref "C7") (pin "1") (pinfunction "1_1") (pintype "passive"))
      (node (ref "C9") (pin "2") (pinfunction "2_2") (pintype "passive"))
      (node (ref "J2") (pin "5") (pinfunction "5_5") (pintype "passive"))
      (node (ref "R13") (pin "1") (pinfunction "1_1") (pintype "passive"))
      (node (ref "R6") (pin "2") (pinfunction "2_2") (pintype "passive"))
      (node (ref "R8") (pin "2") (pinfunction "2_2") (pintype "passive"))
      (node (ref "R9") (pin "2") (pinfunction "2_2") (pintype "passive"))
      (node (ref "U1") (pin "14") (pinfunction "VCCIOA_14") (pintype "power_in"))
      (node (ref "U1") (pin "31") (pinfunction "VCCIOB_31") (pintype "power_in"))
      (node (ref "U2") (pin "4") (pinfunction "OUT_4") (pintype "power_in"))
      (node (ref "U3") (pin "6") (pinfunction "VCC_6") (pintype "power_in"))
      (node (ref "U4") (pin "2") (pinfunction "D_2") (pintype "input"))
      (node (ref "U4") (pin "7") (pinfunction "~{PRE}_7") (pintype "input"))
      (node (ref "U4") (pin "8") (pinfunction "VCC_8") (pintype "power_in"))
    )
    (net (code "76") (name "5V-USB") (class "Default")
      (node (ref "JP2") (pin "1") (pinfunction "VBUS_1") (pintype "power_in"))
      (node (ref "SW1") (pin "3") (pinfunction "3_3") (pintype "passive"))
    )
    (net (code "77") (name "5V0") (class "Default")
      (node (ref "5V") (pin "1") (pinfunction "1_1") (pintype "passive"))
      (node (ref "5V") (pin "2") (pinfunction "2_2") (pintype "passive"))
      (node (ref "C1") (pin "1") (pinfunction "1_1") (pintype "passive"))
      (node (ref "DA1") (pin "6") (pinfunction "C1_6") (pintype "passive"))
      (node (ref "J1") (pin "77") (pinfunction "77_77") (pintype "passive"))
      (node (ref "J1") (pin "82") (pinfunction "82_82") (pintype "passive"))
      (node (ref "J1") (pin "87") (pinfunction "87_87") (pintype "passive"))
      (node (ref "J1") (pin "92") (pinfunction "92_92") (pintype "passive"))
      (node (ref "J1") (pin "96") (pinfunction "96_96") (pintype "passive"))
      (node (ref "L1") (pin "1") (pinfunction "1_1") (pintype "passive"))
      (node (ref "SW1") (pin "2") (pinfunction "2_2") (pintype "passive"))
      (node (ref "U2") (pin "1") (pinfunction "EN_1") (pintype "input"))
      (node (ref "U2") (pin "2") (pinfunction "IN_2") (pintype "power_in"))
    )
    (net (code "78") (name "GND") (class "Default")
      (node (ref "C1") (pin "2") (pinfunction "2_2") (pintype "passive"))
      (node (ref "C10") (pin "1") (pinfunction "1_1") (pintype "passive"))
      (node (ref "C11") (pin "2") (pinfunction "2_2") (pintype "passive"))
      (node (ref "C12") (pin "2") (pinfunction "2_2") (pintype "passive"))
      (node (ref "C2") (pin "2") (pinfunction "2_2") (pintype "passive"))
      (node (ref "C3") (pin "2") (pinfunction "2_2") (pintype "passive"))
      (node (ref "C4") (pin "1") (pinfunction "1_1") (pintype "passive"))
      (node (ref "C5") (pin "2") (pinfunction "2_2") (pintype "passive"))
      (node (ref "C6") (pin "1") (pinfunction "1_1") (pintype "passive"))
      (node (ref "C7") (pin "2") (pinfunction "2_2") (pintype "passive"))
      (node (ref "C8") (pin "1") (pinfunction "1_1") (pintype "passive"))
      (node (ref "C9") (pin "1") (pinfunction "1_1") (pintype "passive"))
      (node (ref "DA1") (pin "3") (pinfunction "A2_3") (pintype "passive"))
      (node (ref "GND 1") (pin "1") (pinfunction "1_1") (pintype "passive"))
      (node (ref "GND 1") (pin "2") (pinfunction "2_2") (pintype "passive"))
      (node (ref "GND 1") (pin "3") (pinfunction "3_3") (pintype "passive"))
      (node (ref "GND 2") (pin "1") (pinfunction "1_1") (pintype "passive"))
      (node (ref "GND 2") (pin "2") (pinfunction "2_2") (pintype "passive"))
      (node (ref "GND 2") (pin "3") (pinfunction "3_3") (pintype "passive"))
      (node (ref "GND 3") (pin "1") (pinfunction "1_1") (pintype "passive"))
      (node (ref "GND 3") (pin "2") (pinfunction "2_2") (pintype "passive"))
      (node (ref "GND 4") (pin "1") (pinfunction "1_1") (pintype "passive"))
      (node (ref "GND 4") (pin "2") (pinfunction "2_2") (pintype "passive"))
      (node (ref "J1") (pin "10") (pinfunction "10_10") (pintype "passive"))
      (node (ref "J1") (pin "12") (pinfunction "12_12") (pintype "passive"))
      (node (ref "J1") (pin "14") (pinfunction "14_14") (pintype "passive"))
      (node (ref "J1") (pin "27") (pinfunction "27_27") (pintype "passive"))
      (node (ref "J1") (pin "37") (pinfunction "37_37") (pintype "passive"))
      (node (ref "J1") (pin "47") (pinfunction "47_47") (pintype "passive"))
      (node (ref "J1") (pin "58") (pinfunction "58_58") (pintype "passive"))
      (node (ref "J1") (pin "60") (pinfunction "60_60") (pintype "passive"))
      (node (ref "J1") (pin "62") (pinfunction "62_62") (pintype "passive"))
      (node (ref "J1") (pin "64") (pinfunction "64_64") (pintype "passive"))
      (node (ref "J1") (pin "8") (pinfunction "8_8") (pintype "passive"))
      (node (ref "J2") (pin "10") (pinfunction "10_10") (pintype "passive"))
      (node (ref "J2") (pin "12") (pinfunction "12_12") (pintype "passive"))
      (node (ref "J2") (pin "4") (pinfunction "4_4") (pintype "passive"))
      (node (ref "J2") (pin "8") (pinfunction "8_8") (pintype "passive"))
      (node (ref "JP1") (pin "2") (pinfunction "2_2") (pintype "passive"))
      (node (ref "JP1") (pin "3") (pinfunction "3_3") (pintype "passive"))
      (node (ref "JP2") (pin "4") (pinfunction "GND_4") (pintype "power_in"))
      (node (ref "LD1") (pin "1") (pinfunction "NEG_1") (pintype "bidirectional"))
      (node (ref "R10") (pin "1") (pinfunction "1_1") (pintype "passive"))
      (node (ref "R11") (pin "1") (pinfunction "1_1") (pintype "passive"))
      (node (ref "R12") (pin "1") (pinfunction "1_1") (pintype "passive"))
      (node (ref "R14") (pin "2") (pinfunction "2_2") (pintype "passive"))
      (node (ref "R15") (pin "1") (pinfunction "1_1") (pintype "passive"))
      (node (ref "R16") (pin "1") (pinfunction "1_1") (pintype "passive"))
      (node (ref "R17") (pin "1") (pinfunction "1_1") (pintype "passive"))
      (node (ref "R18") (pin "1") (pinfunction "1_1") (pintype "passive"))
      (node (ref "U1") (pin "10") (pinfunction "SI/WUA_10") (pintype "input"))
      (node (ref "U1") (pin "18") (pinfunction "GND_18") (pintype "power_in"))
      (node (ref "U1") (pin "25") (pinfunction "GND_25") (pintype "power_in"))
      (node (ref "U1") (pin "26") (pinfunction "SI/WUB_26") (pintype "input"))
      (node (ref "U1") (pin "34") (pinfunction "GND_34") (pintype "power_in"))
      (node (ref "U1") (pin "45") (pinfunction "AGND_45") (pintype "power_in"))
      (node (ref "U1") (pin "47") (pinfunction "TEST_47") (pintype "input"))
      (node (ref "U1") (pin "9") (pinfunction "GND_9") (pintype "power_in"))
      (node (ref "U2") (pin "3") (pinfunction "GND_3") (pintype "power_in"))
      (node (ref "U2") (pin "6") (pinfunction "GND_6") (pintype "power_in"))
      (node (ref "U3") (pin "2") (pinfunction "VSS_2") (pintype "power_in"))
      (node (ref "U4") (pin "4") (pinfunction "GND_4") (pintype "passive"))
      (node (ref "X1") (pin "2") (pinfunction "2_2") (pintype "power_in"))
    )
    (net (code "79") (name "Net-(C4-Pad2)") (class "Default")
      (node (ref "C4") (pin "2") (pinfunction "2_2") (pintype "passive"))
      (node (ref "C5") (pin "1") (pinfunction "1_1") (pintype "passive"))
      (node (ref "L1") (pin "2") (pinfunction "2_2") (pintype "passive"))
      (node (ref "R1") (pin "2") (pinfunction "2_2") (pintype "passive"))
      (node (ref "U1") (pin "3") (pinfunction "VCC_3") (pintype "power_in"))
      (node (ref "U1") (pin "42") (pinfunction "VCC_42") (pintype "power_in"))
    )
    (net (code "80") (name "Net-(J8-Pad2)") (class "Default")
      (node (ref "J8") (pin "2") (pinfunction "2_2") (pintype "passive"))
      (node (ref "R14") (pin "1") (pinfunction "1_1") (pintype "passive"))
    )
    (net (code "81") (name "Net-(J18-Pad2)") (class "Default")
      (node (ref "J18") (pin "2") (pinfunction "2_2") (pintype "passive"))
      (node (ref "R12") (pin "2") (pinfunction "2_2") (pintype "passive"))
    )
    (net (code "82") (name "Net-(J29-Pad2)") (class "Default")
      (node (ref "J29") (pin "2") (pinfunction "2_2") (pintype "passive"))
      (node (ref "R11") (pin "2") (pinfunction "2_2") (pintype "passive"))
    )
    (net (code "83") (name "Net-(J34-Pad2)") (class "Default")
      (node (ref "J34") (pin "2") (pinfunction "2_2") (pintype "passive"))
      (node (ref "R10") (pin "2") (pinfunction "2_2") (pintype "passive"))
    )
    (net (code "84") (name "Net-(J84-Pad2)") (class "Default")
      (node (ref "J84") (pin "2") (pinfunction "2_2") (pintype "passive"))
      (node (ref "R18") (pin "2") (pinfunction "2_2") (pintype "passive"))
    )
    (net (code "85") (name "Net-(J85-Pad2)") (class "Default")
      (node (ref "J85") (pin "2") (pinfunction "2_2") (pintype "passive"))
      (node (ref "R17") (pin "2") (pinfunction "2_2") (pintype "passive"))
    )
    (net (code "86") (name "Net-(J86-Pad2)") (class "Default")
      (node (ref "J86") (pin "2") (pinfunction "2_2") (pintype "passive"))
      (node (ref "R16") (pin "2") (pinfunction "2_2") (pintype "passive"))
    )
    (net (code "87") (name "Net-(J87-Pad2)") (class "Default")
      (node (ref "J87") (pin "2") (pinfunction "2_2") (pintype "passive"))
      (node (ref "R15") (pin "2") (pinfunction "2_2") (pintype "passive"))
    )
    (net (code "88") (name "Net-(JP1-Pad1)") (class "Default")
      (node (ref "JP1") (pin "1") (pinfunction "1_1") (pintype "passive"))
      (node (ref "SW1") (pin "1") (pinfunction "1_1") (pintype "passive"))
    )
    (net (code "89") (name "Net-(JP2-D+)") (class "Default")
      (node (ref "DA1") (pin "1") (pinfunction "A1_1") (pintype "passive"))
      (node (ref "DA1") (pin "5") (pinfunction "C2_5") (pintype "passive"))
      (node (ref "JP2") (pin "3") (pinfunction "D+_3") (pintype "bidirectional"))
      (node (ref "R3") (pin "2") (pinfunction "2_2") (pintype "passive"))
    )
    (net (code "90") (name "Net-(JP2-D-)") (class "Default")
      (node (ref "DA1") (pin "2") (pinfunction "A1_2") (pintype "passive"))
      (node (ref "DA1") (pin "4") (pinfunction "C2_4") (pintype "passive"))
      (node (ref "JP2") (pin "2") (pinfunction "D-_2") (pintype "bidirectional"))
      (node (ref "R2") (pin "2") (pinfunction "2_2") (pintype "passive"))
    )
    (net (code "91") (name "Net-(LD1-POS)") (class "Default")
      (node (ref "LD1") (pin "2") (pinfunction "POS_2") (pintype "bidirectional"))
      (node (ref "R9") (pin "1") (pinfunction "1_1") (pintype "passive"))
    )
    (net (code "92") (name "Net-(U1-3V3OUT)") (class "Default")
      (node (ref "C8") (pin "2") (pinfunction "2_2") (pintype "passive"))
      (node (ref "U1") (pin "6") (pinfunction "3V3OUT_6") (pintype "output"))
    )
    (net (code "93") (name "Net-(U1-ACBUS2)") (class "Default")
      (node (ref "U1") (pin "12") (pinfunction "ACBUS2_12") (pintype "bidirectional"))
      (node (ref "U4") (pin "5") (pinfunction "Q_5") (pintype "output"))
    )
    (net (code "94") (name "Net-(U1-ACBUS3)") (class "Default")
      (node (ref "U1") (pin "11") (pinfunction "ACBUS3_11") (pintype "bidirectional"))
      (node (ref "U4") (pin "1") (pinfunction "CLK_1") (pintype "input"))
    )
    (net (code "95") (name "Net-(U1-AVCC)") (class "Default")
      (node (ref "C6") (pin "2") (pinfunction "2_2") (pintype "passive"))
      (node (ref "R1") (pin "1") (pinfunction "1_1") (pintype "passive"))
      (node (ref "U1") (pin "46") (pinfunction "AVCC_46") (pintype "power_in"))
    )
    (net (code "96") (name "Net-(U1-BDBUS0)") (class "Default")
      (node (ref "J9") (pin "1") (pinfunction "1_1") (pintype "passive"))
      (node (ref "U1") (pin "40") (pinfunction "BDBUS0_40") (pintype "bidirectional"))
    )
    (net (code "97") (name "Net-(U1-EECS)") (class "Default")
      (node (ref "U1") (pin "48") (pinfunction "EECS_48") (pintype "bidirectional"))
      (node (ref "U3") (pin "5") (pinfunction "CS_5") (pintype "input"))
    )
    (net (code "98") (name "Net-(U1-EEDATA)") (class "Default")
      (node (ref "R7") (pin "2") (pinfunction "2_2") (pintype "passive"))
      (node (ref "U1") (pin "2") (pinfunction "EEDATA_2") (pintype "bidirectional"))
      (node (ref "U3") (pin "3") (pinfunction "DI_3") (pintype "input"))
    )
    (net (code "99") (name "Net-(U1-EESK)") (class "Default")
      (node (ref "U1") (pin "1") (pinfunction "EESK_1") (pintype "output"))
      (node (ref "U3") (pin "4") (pinfunction "CLK_4") (pintype "input"))
    )
    (net (code "100") (name "Net-(U1-USBDM)") (class "Default")
      (node (ref "R2") (pin "1") (pinfunction "1_1") (pintype "passive"))
      (node (ref "U1") (pin "8") (pinfunction "USBDM_8") (pintype "bidirectional"))
    )
    (net (code "101") (name "Net-(U1-USBDP)") (class "Default")
      (node (ref "R3") (pin "1") (pinfunction "1_1") (pintype "passive"))
      (node (ref "R4") (pin "1") (pinfunction "1_1") (pintype "passive"))
      (node (ref "U1") (pin "7") (pinfunction "USBDP_7") (pintype "bidirectional"))
    )
    (net (code "102") (name "Net-(U1-XTIN)") (class "Default")
      (node (ref "R5") (pin "1") (pinfunction "1_1") (pintype "passive"))
      (node (ref "U1") (pin "43") (pinfunction "XTIN_43") (pintype "input"))
      (node (ref "X1") (pin "1") (pinfunction "1_1") (pintype "passive"))
    )
    (net (code "103") (name "Net-(U1-XTOUT)") (class "Default")
      (node (ref "R5") (pin "2") (pinfunction "2_2") (pintype "passive"))
      (node (ref "U1") (pin "44") (pinfunction "XTOUT_44") (pintype "output"))
      (node (ref "X1") (pin "3") (pinfunction "3_3") (pintype "passive"))
    )
    (net (code "104") (name "Net-(U1-~{RESET})") (class "Default")
      (node (ref "J8") (pin "1") (pinfunction "1_1") (pintype "passive"))
      (node (ref "R13") (pin "2") (pinfunction "2_2") (pintype "passive"))
      (node (ref "U1") (pin "4") (pinfunction "~{RESET}_4") (pintype "input"))
    )
    (net (code "105") (name "Net-(U1-~{RSTOUT})") (class "Default")
      (node (ref "R4") (pin "2") (pinfunction "2_2") (pintype "passive"))
      (node (ref "U1") (pin "5") (pinfunction "~{RSTOUT}_5") (pintype "output"))
    )
    (net (code "106") (name "Net-(U2-NR)") (class "Default")
      (node (ref "C3") (pin "1") (pinfunction "1_1") (pintype "passive"))
      (node (ref "U2") (pin "5") (pinfunction "NR_5") (pintype "passive"))
    )
    (net (code "107") (name "Net-(U3-DO)") (class "Default")
      (node (ref "R6") (pin "1") (pinfunction "1_1") (pintype "passive"))
      (node (ref "R7") (pin "1") (pinfunction "1_1") (pintype "passive"))
      (node (ref "U3") (pin "1") (pinfunction "DO_1") (pintype "tri_state"))
    )
    (net (code "108") (name "Net-(U4-~{CLR})") (class "Default")
      (node (ref "C11") (pin "1") (pinfunction "1_1") (pintype "passive"))
      (node (ref "R8") (pin "1") (pinfunction "1_1") (pintype "passive"))
      (node (ref "U4") (pin "6") (pinfunction "~{CLR}_6") (pintype "input"))
    )
    (net (code "109") (name "unconnected-(J1-Pad3)") (class "Default")
      (node (ref "J1") (pin "3") (pinfunction "3_3") (pintype "passive+no_connect"))
    )
    (net (code "110") (name "unconnected-(J1-Pad4)") (class "Default")
      (node (ref "J1") (pin "4") (pinfunction "4_4") (pintype "passive+no_connect"))
    )
    (net (code "111") (name "unconnected-(J1-Pad5)") (class "Default")
      (node (ref "J1") (pin "5") (pinfunction "5_5") (pintype "passive+no_connect"))
    )
    (net (code "112") (name "unconnected-(J1-Pad16)") (class "Default")
      (node (ref "J1") (pin "16") (pinfunction "16_16") (pintype "passive+no_connect"))
    )
    (net (code "113") (name "unconnected-(J1-Pad51)") (class "Default")
      (node (ref "J1") (pin "51") (pinfunction "51_51") (pintype "passive+no_connect"))
    )
    (net (code "114") (name "unconnected-(J1-Pad53)") (class "Default")
      (node (ref "J1") (pin "53") (pinfunction "53_53") (pintype "passive+no_connect"))
    )
    (net (code "115") (name "unconnected-(J1-Pad54)") (class "Default")
      (node (ref "J1") (pin "54") (pinfunction "54_54") (pintype "passive+no_connect"))
    )
    (net (code "116") (name "unconnected-(J1-Pad55)") (class "Default")
      (node (ref "J1") (pin "55") (pinfunction "55_55") (pintype "passive+no_connect"))
    )
    (net (code "117") (name "unconnected-(J1-Pad56)") (class "Default")
      (node (ref "J1") (pin "56") (pinfunction "56_56") (pintype "passive+no_connect"))
    )
    (net (code "118") (name "unconnected-(J1-Pad66)") (class "Default")
      (node (ref "J1") (pin "66") (pinfunction "66_66") (pintype "passive+no_connect"))
    )
    (net (code "119") (name "unconnected-(J2-Pad6)") (class "Default")
      (node (ref "J2") (pin "6") (pinfunction "6_6") (pintype "passive+no_connect"))
    )
    (net (code "120") (name "unconnected-(U1-ACBUS0-Pad15)") (class "Default")
      (node (ref "U1") (pin "15") (pinfunction "ACBUS0_15") (pintype "bidirectional+no_connect"))
    )
    (net (code "121") (name "unconnected-(U1-ACBUS1-Pad13)") (class "Default")
      (node (ref "U1") (pin "13") (pinfunction "ACBUS1_13") (pintype "bidirectional+no_connect"))
    )
    (net (code "122") (name "unconnected-(U1-ADBUS5-Pad19)") (class "Default")
      (node (ref "U1") (pin "19") (pinfunction "ADBUS5_19") (pintype "bidirectional+no_connect"))
    )
    (net (code "123") (name "unconnected-(U1-ADBUS6-Pad17)") (class "Default")
      (node (ref "U1") (pin "17") (pinfunction "ADBUS6_17") (pintype "bidirectional+no_connect"))
    )
    (net (code "124") (name "unconnected-(U1-ADBUS7-Pad16)") (class "Default")
      (node (ref "U1") (pin "16") (pinfunction "ADBUS7_16") (pintype "bidirectional+no_connect"))
    )
    (net (code "125") (name "unconnected-(U1-BCBUS0-Pad30)") (class "Default")
      (node (ref "U1") (pin "30") (pinfunction "BCBUS0_30") (pintype "bidirectional+no_connect"))
    )
    (net (code "126") (name "unconnected-(U1-BCBUS1-Pad29)") (class "Default")
      (node (ref "U1") (pin "29") (pinfunction "BCBUS1_29") (pintype "bidirectional+no_connect"))
    )
    (net (code "127") (name "unconnected-(U1-BCBUS2-Pad28)") (class "Default")
      (node (ref "U1") (pin "28") (pinfunction "BCBUS2_28") (pintype "bidirectional+no_connect"))
    )
    (net (code "128") (name "unconnected-(U1-BCBUS3-Pad27)") (class "Default")
      (node (ref "U1") (pin "27") (pinfunction "BCBUS3_27") (pintype "bidirectional+no_connect"))
    )
    (net (code "129") (name "unconnected-(U1-BDBUS2-Pad38)") (class "Default")
      (node (ref "U1") (pin "38") (pinfunction "BDBUS2_38") (pintype "bidirectional+no_connect"))
    )
    (net (code "130") (name "unconnected-(U1-BDBUS3-Pad37)") (class "Default")
      (node (ref "U1") (pin "37") (pinfunction "BDBUS3_37") (pintype "bidirectional+no_connect"))
    )
    (net (code "131") (name "unconnected-(U1-BDBUS4-Pad36)") (class "Default")
      (node (ref "U1") (pin "36") (pinfunction "BDBUS4_36") (pintype "bidirectional+no_connect"))
    )
    (net (code "132") (name "unconnected-(U1-BDBUS5-Pad35)") (class "Default")
      (node (ref "U1") (pin "35") (pinfunction "BDBUS5_35") (pintype "bidirectional+no_connect"))
    )
    (net (code "133") (name "unconnected-(U1-BDBUS6-Pad33)") (class "Default")
      (node (ref "U1") (pin "33") (pinfunction "BDBUS6_33") (pintype "bidirectional+no_connect"))
    )
    (net (code "134") (name "unconnected-(U1-BDBUS7-Pad32)") (class "Default")
      (node (ref "U1") (pin "32") (pinfunction "BDBUS7_32") (pintype "bidirectional+no_connect"))
    )
    (net (code "135") (name "unconnected-(U1-~{PWREN}-Pad41)") (class "Default")
      (node (ref "U1") (pin "41") (pinfunction "~{PWREN}_41") (pintype "output+no_connect"))
    )
    (net (code "136") (name "unconnected-(U4-~{Q}-Pad3)") (class "Default")
      (node (ref "U4") (pin "3") (pinfunction "~{Q}_3") (pintype "output+no_connect"))
    )
  )
)
